# cnc_1_0_0.net
KiCad netlist of a schematic drawn in EAGLE
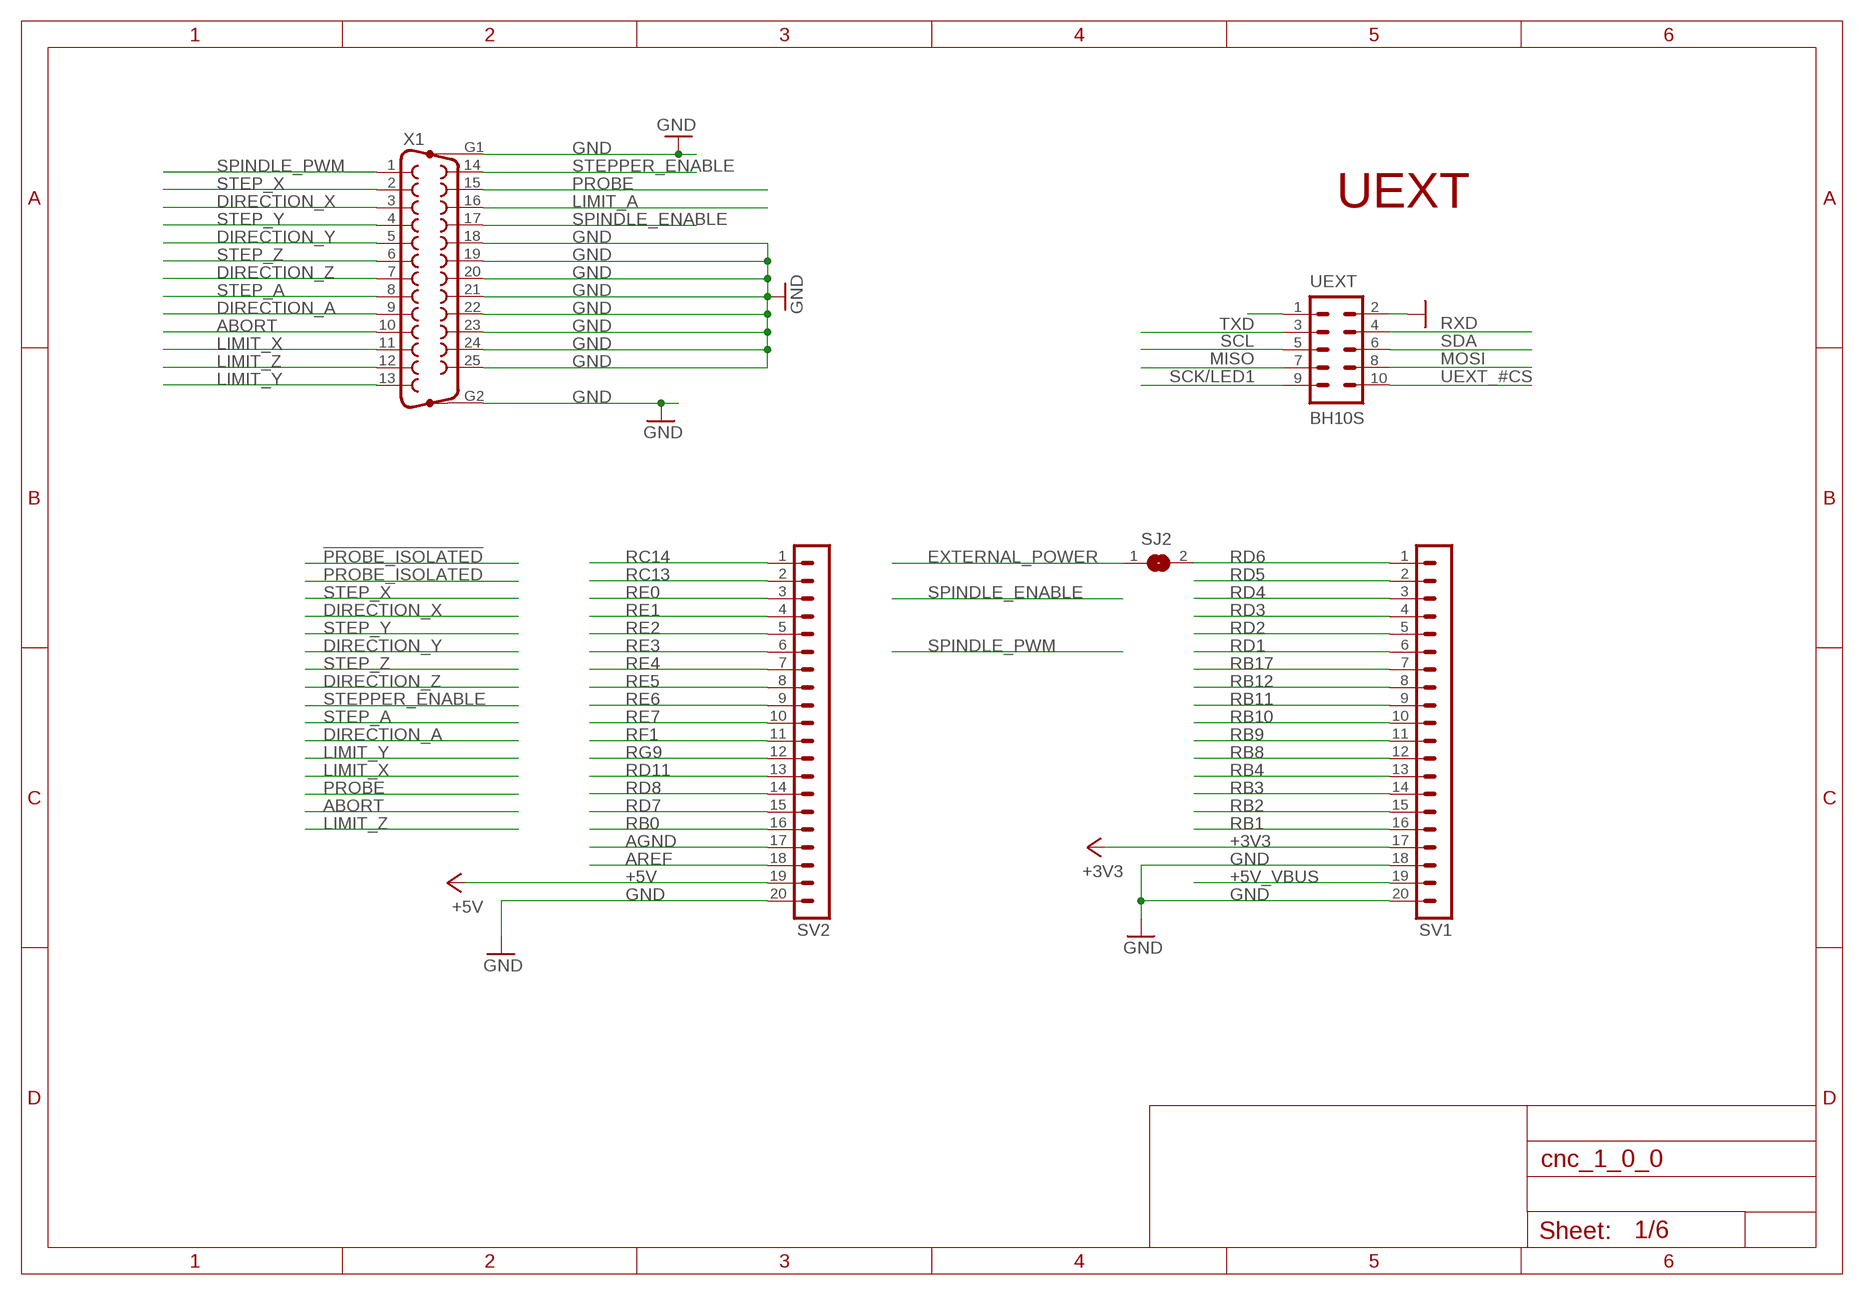
[diagram p0: schematic, sheet 1]
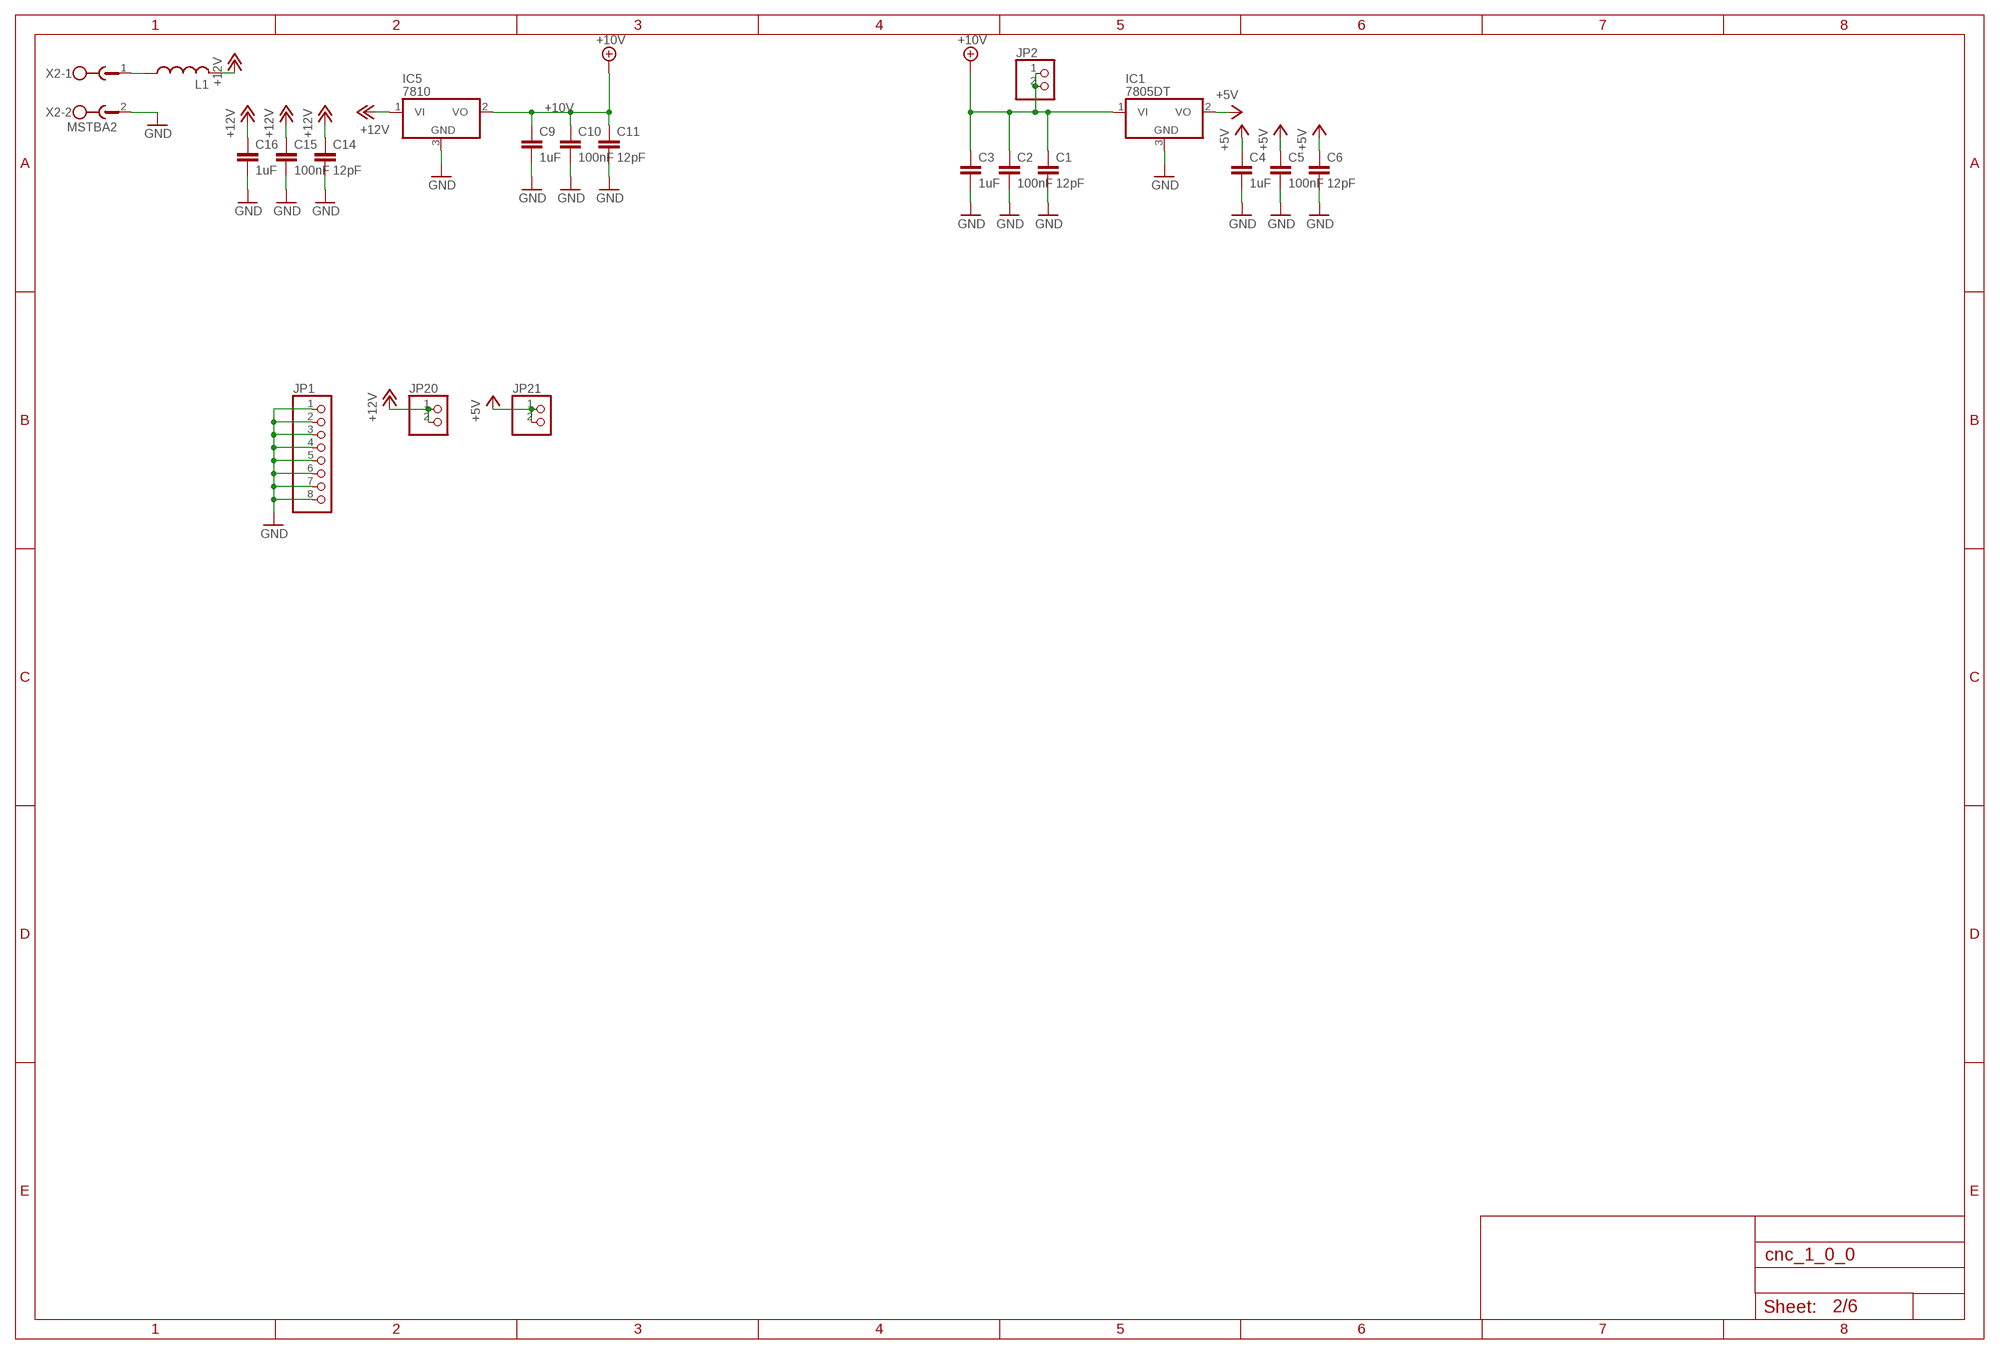
[diagram p1: schematic, sheet 2]
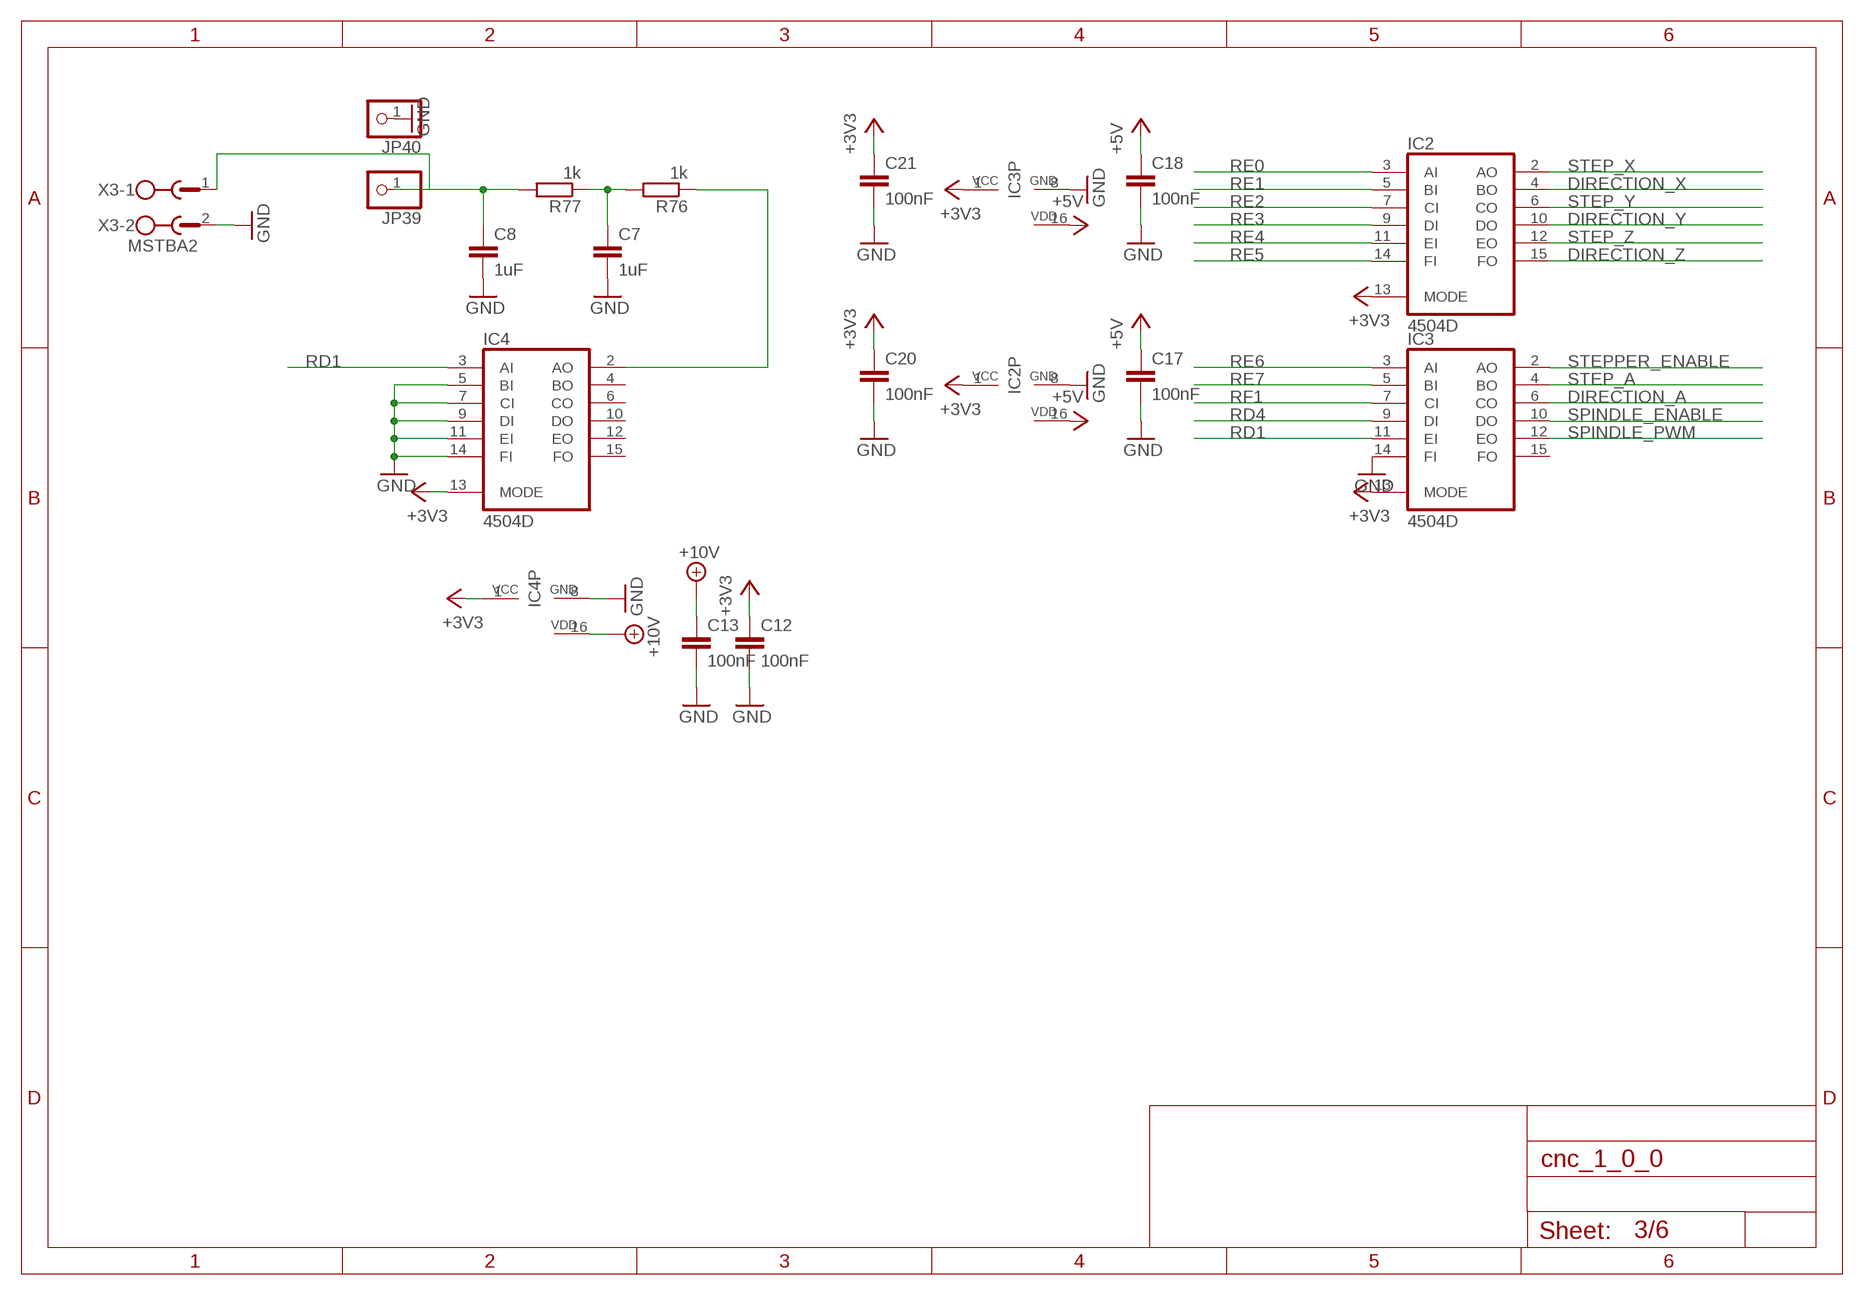
[diagram p2: schematic, sheet 3]
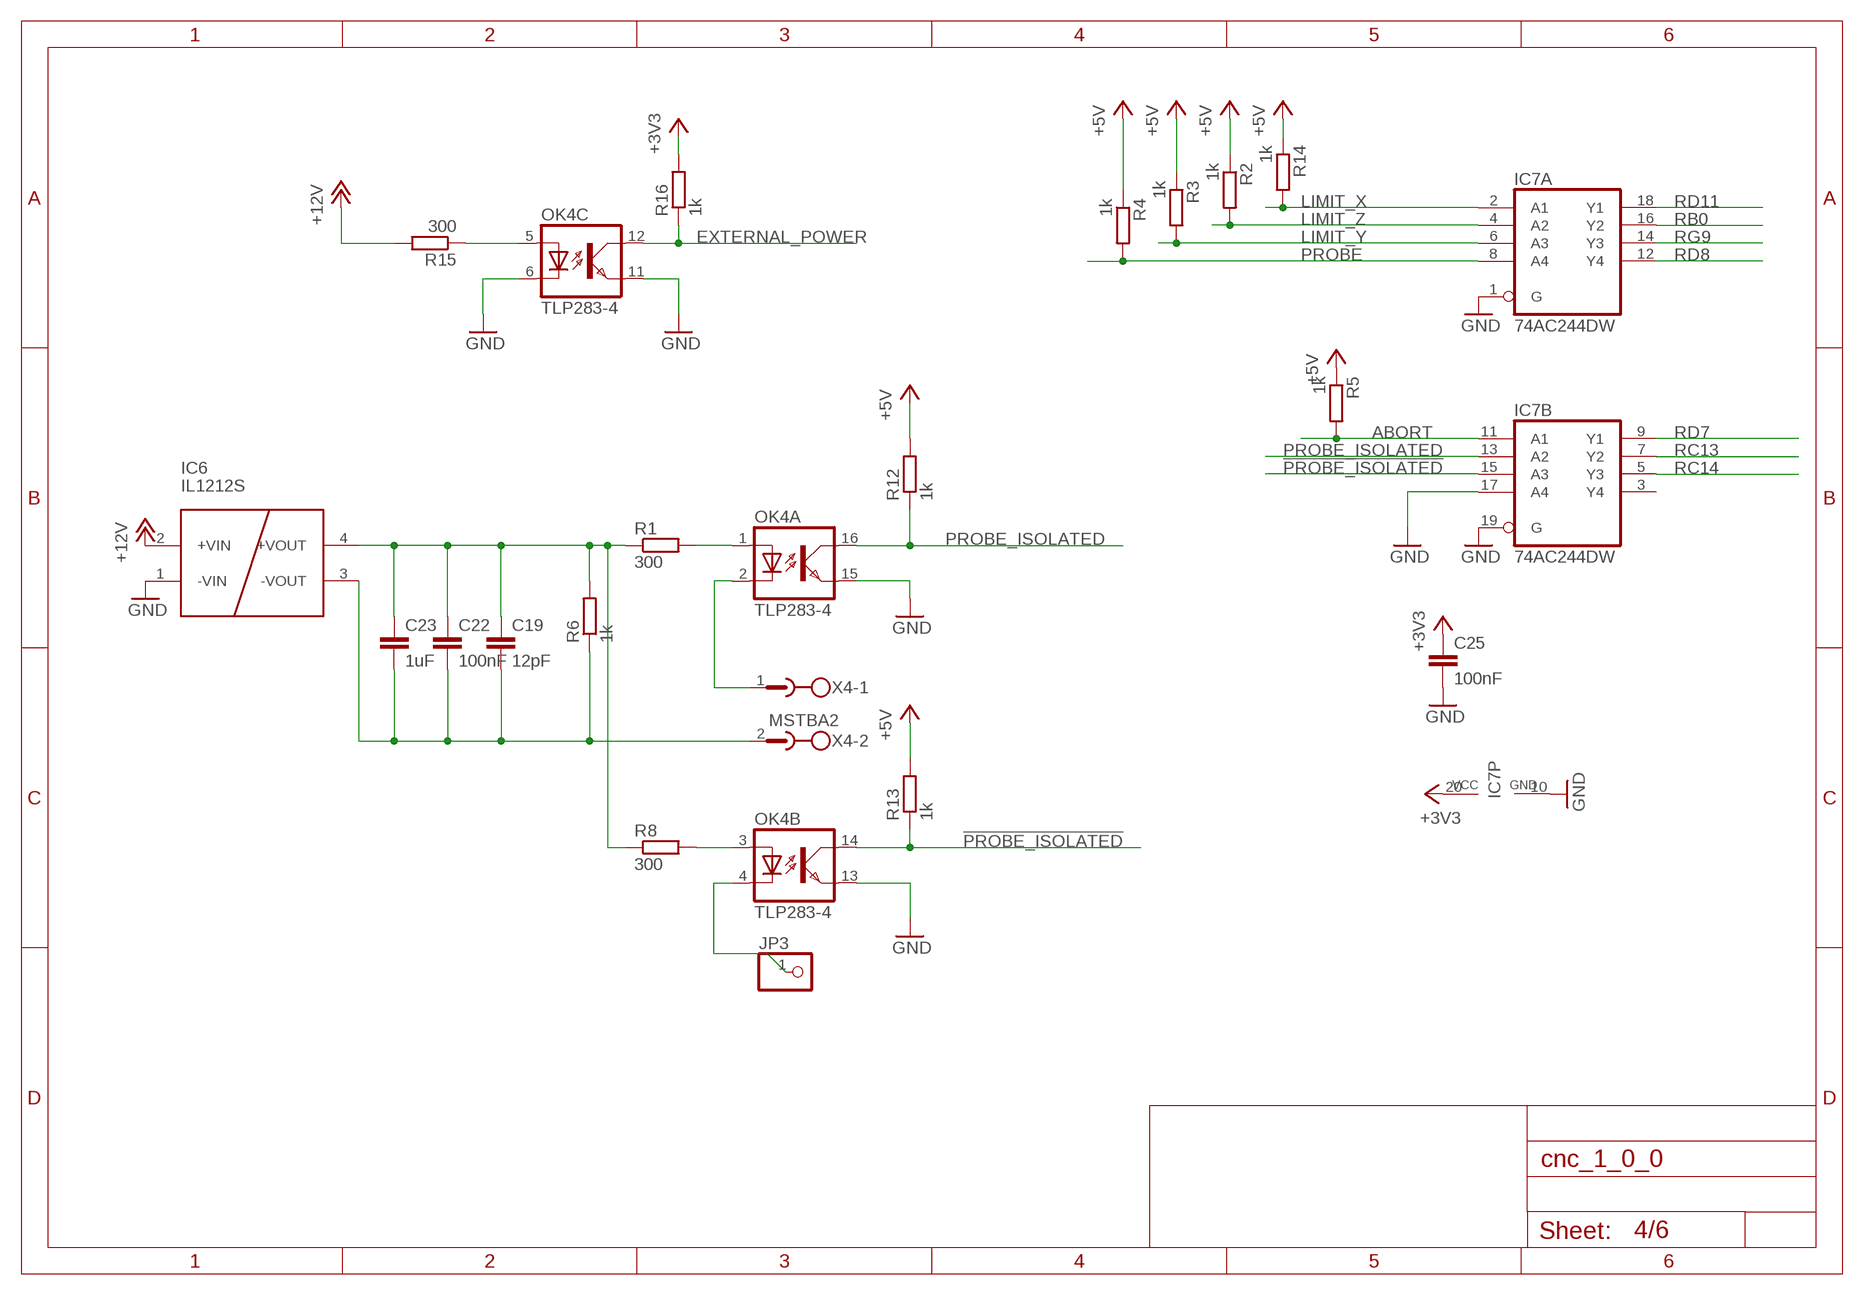
[diagram p3: schematic, sheet 4]
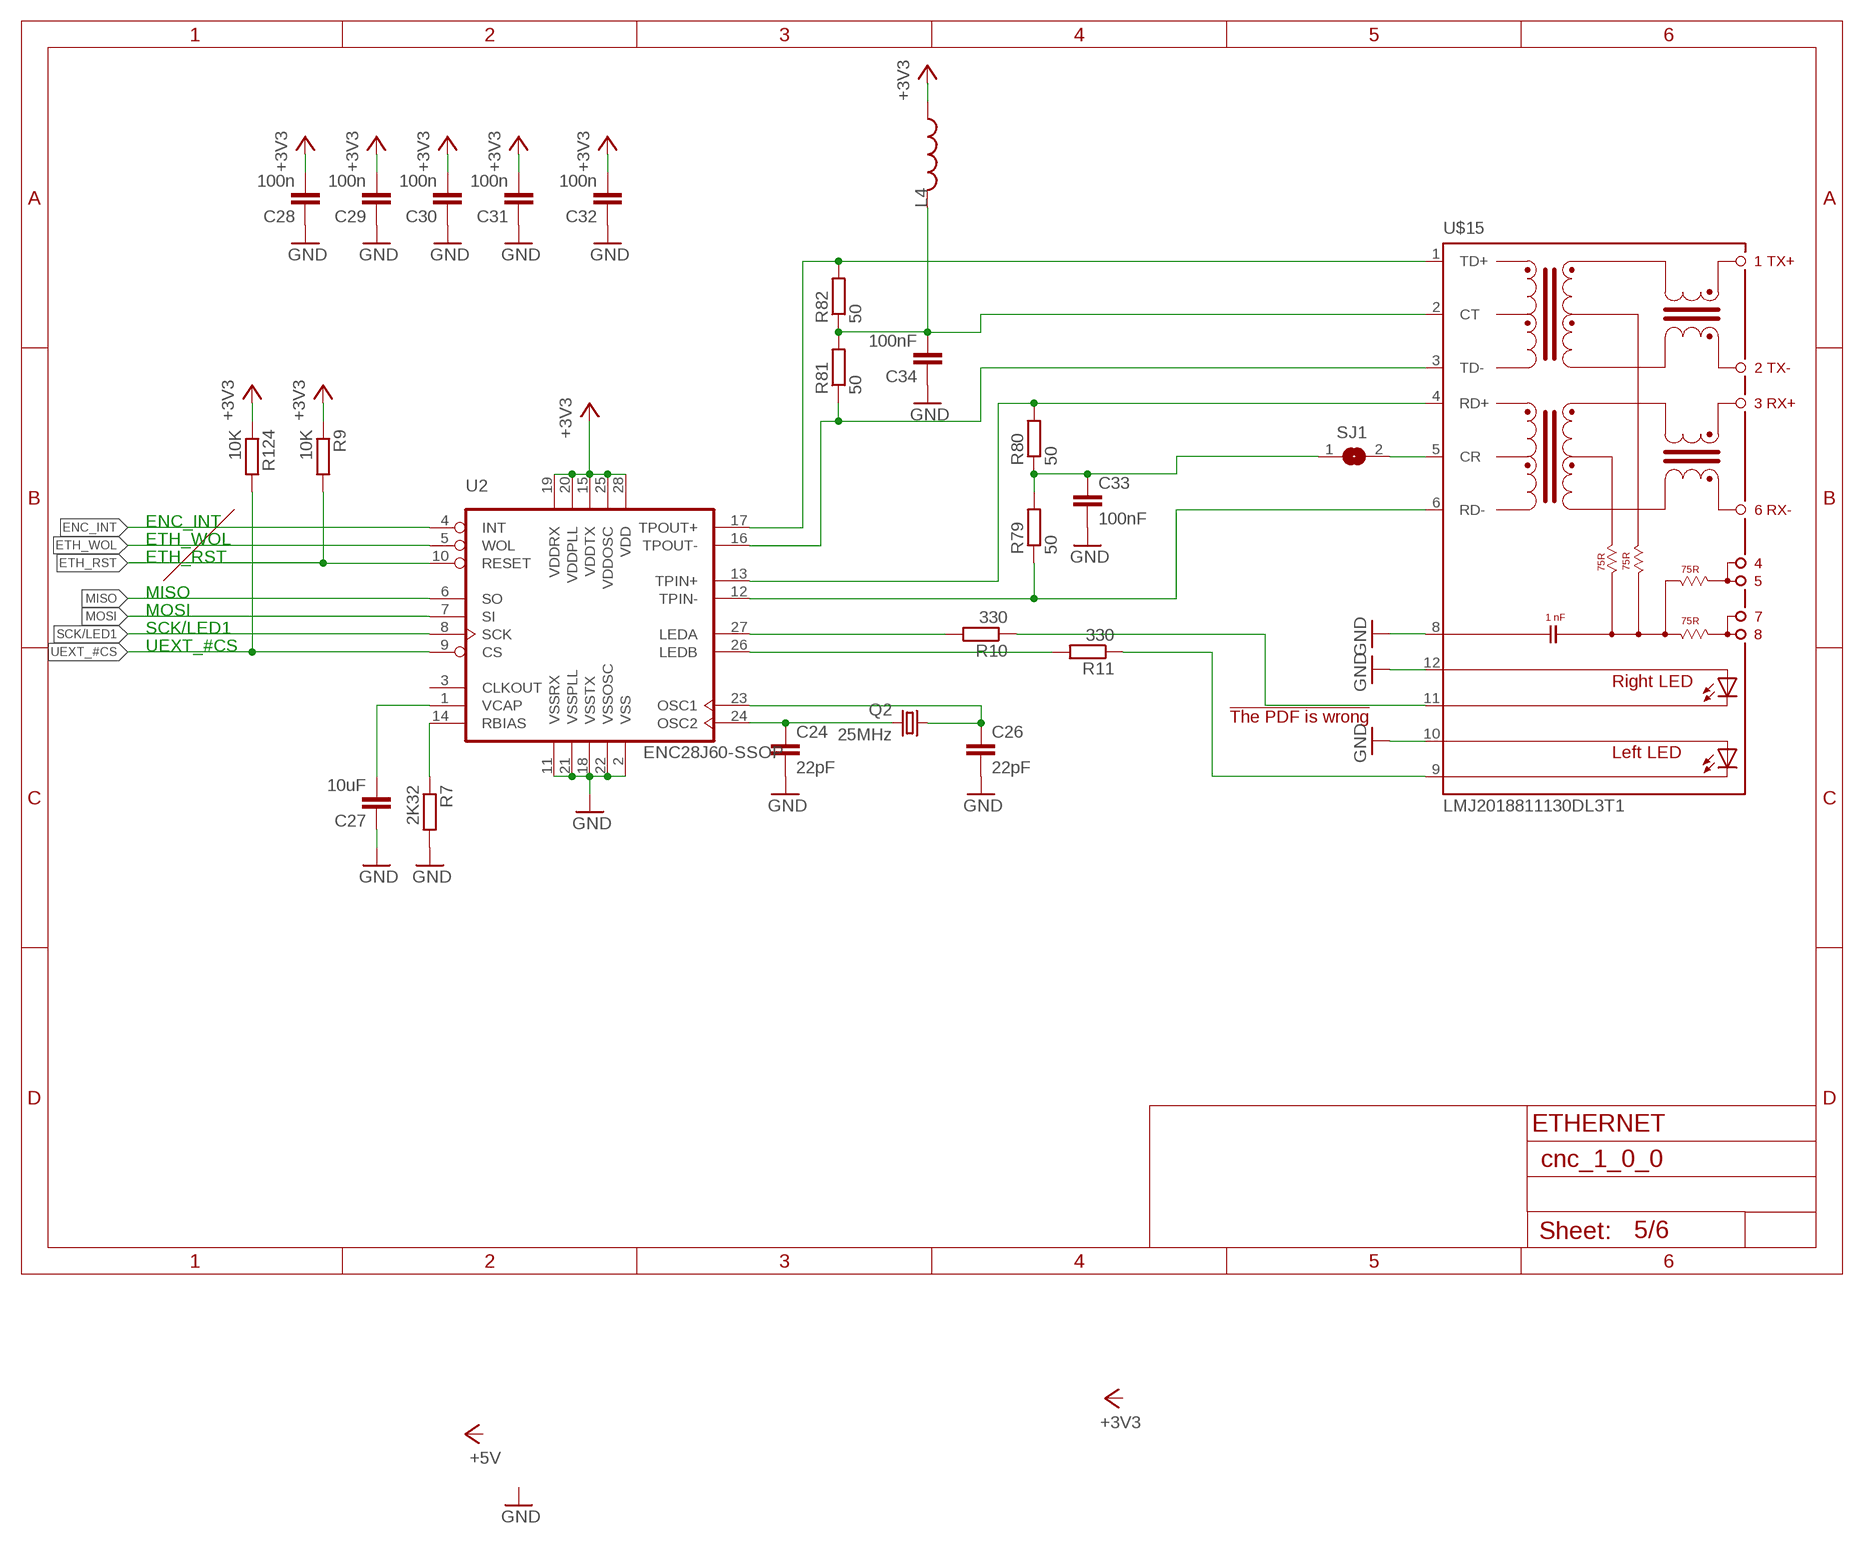
[diagram p4: schematic, sheet 5]
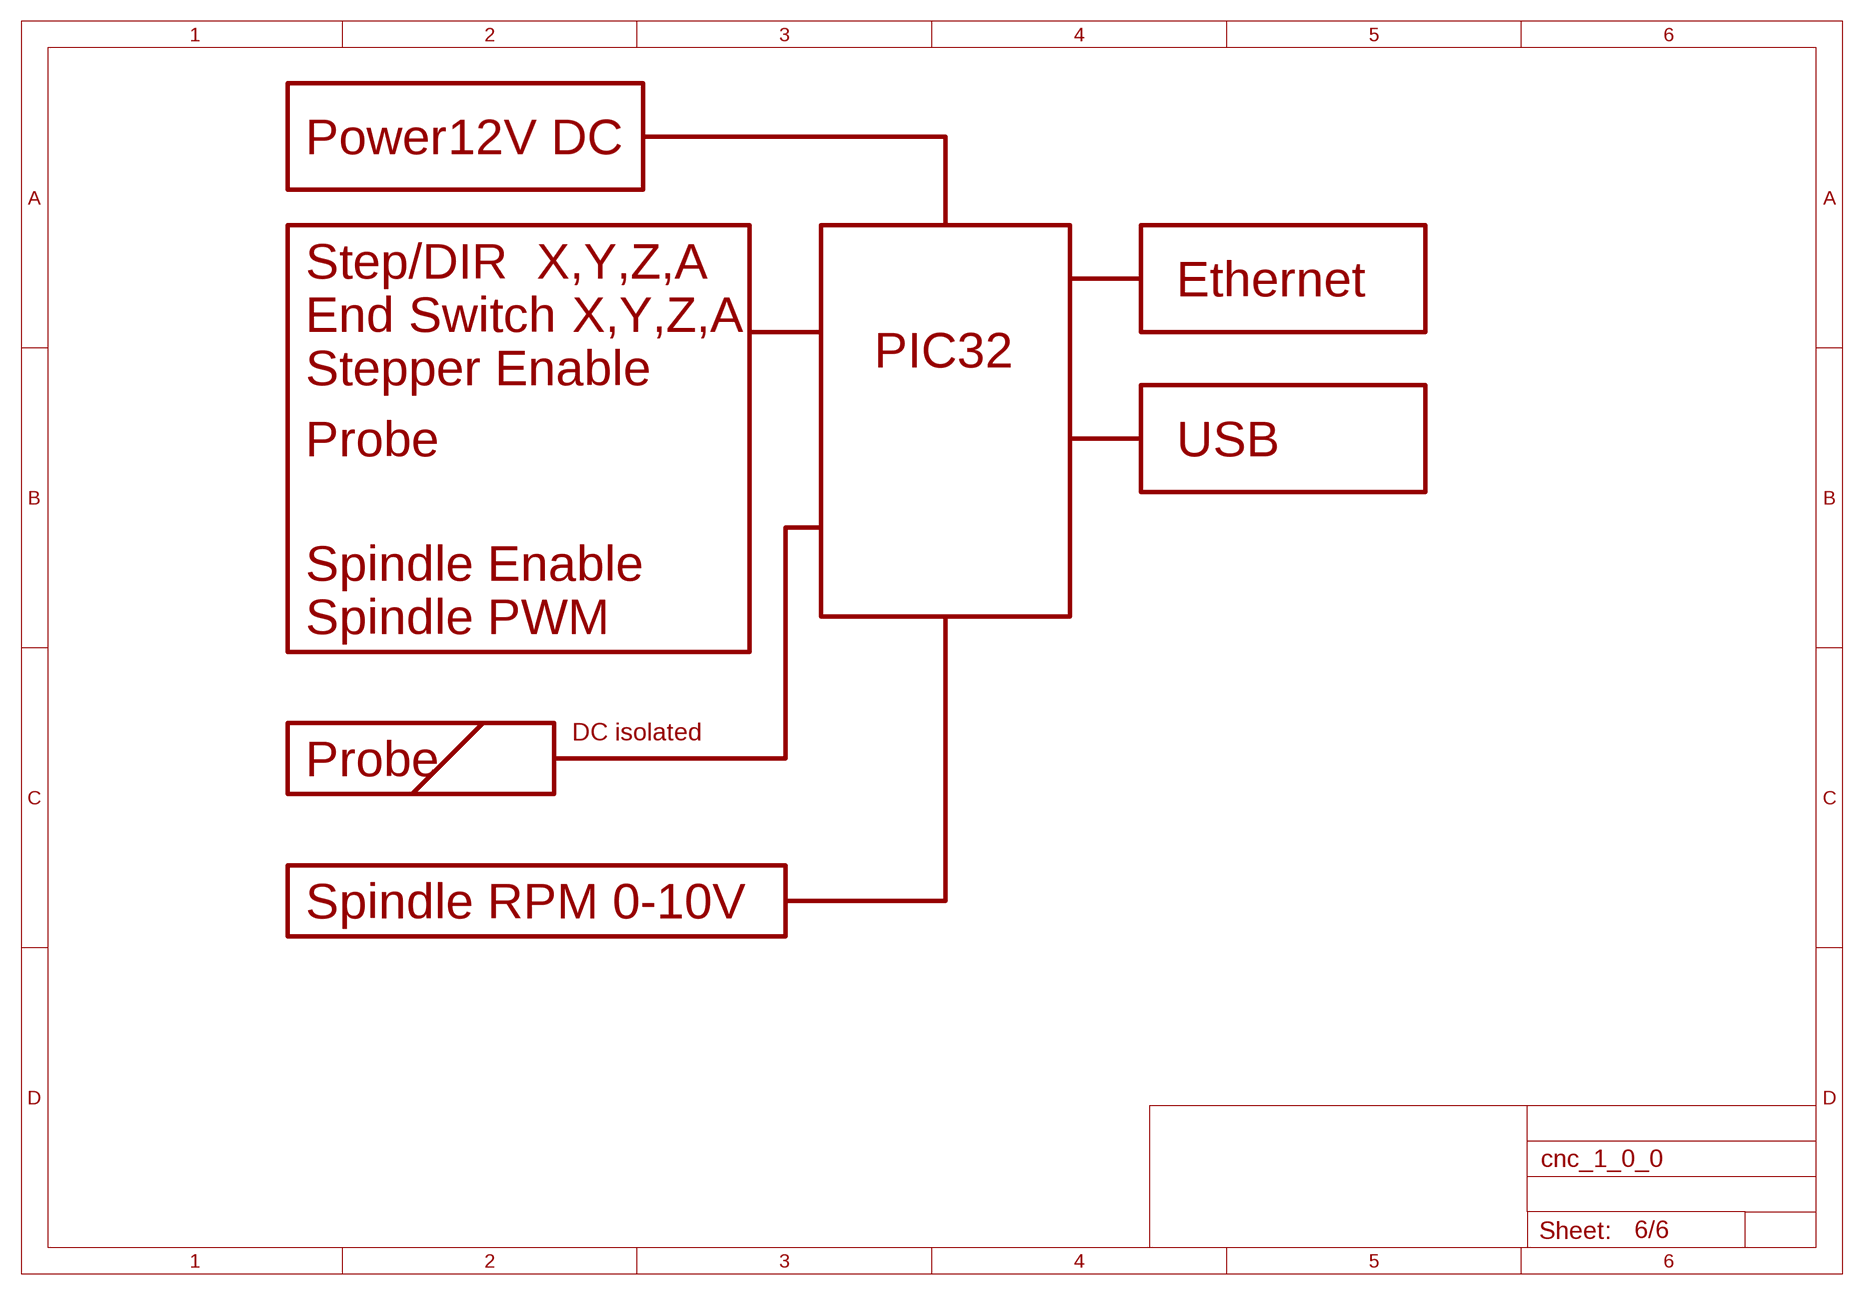
[diagram p5: schematic, sheet 6]

(export (version "E")
  (design (tool "Eeschema 10.0.6"))
  (components
    (comp (ref "C19")
      (value "12pF")
      (footprint "eagle-import:C0805K")
      (libsource (lib "eagle-import") (part "C-EUC0805K"))
    )
    (comp (ref "C22")
      (value "100nF")
      (footprint "eagle-import:C0805K")
      (libsource (lib "eagle-import") (part "C-EUC0805K"))
    )
    (comp (ref "C23")
      (value "1uF")
      (footprint "eagle-import:C0805K")
      (libsource (lib "eagle-import") (part "C-EUC0805K"))
    )
    (comp (ref "C25")
      (value "100nF")
      (footprint "eagle-import:C0805K")
      (libsource (lib "eagle-import") (part "C-EUC0805K"))
    )
    (comp (ref "IC6")
      (value "IL1212S")
      (footprint "eagle-import:SIL4")
      (libsource (lib "eagle-import") (part "IL0512S"))
    )
    (comp (ref "IC7")
      (value "74AC244DW")
      (footprint "eagle-import:SO20W")
      (libsource (lib "eagle-import") (part "74244DWAC"))
    )
    (comp (ref "JP3")
      (value "PINHD-1X1")
      (footprint "eagle-import:1X01")
      (libsource (lib "eagle-import") (part "PINHD-1X1"))
    )
    (comp (ref "OK4")
      (value "TLP283-4")
      (footprint "eagle-import:MINI-FLAT-16")
      (libsource (lib "eagle-import") (part "TLP283-4"))
    )
    (comp (ref "R1")
      (value "300")
      (footprint "eagle-import:R0805")
      (libsource (lib "eagle-import") (part "R-EU_R0805"))
    )
    (comp (ref "R2")
      (value "1k")
      (footprint "eagle-import:R0805")
      (libsource (lib "eagle-import") (part "R-EU_R0805"))
    )
    (comp (ref "R3")
      (value "1k")
      (footprint "eagle-import:R0805")
      (libsource (lib "eagle-import") (part "R-EU_R0805"))
    )
    (comp (ref "R4")
      (value "1k")
      (footprint "eagle-import:R0805")
      (libsource (lib "eagle-import") (part "R-EU_R0805"))
    )
    (comp (ref "R5")
      (value "1k")
      (footprint "eagle-import:R0805")
      (libsource (lib "eagle-import") (part "R-EU_R0805"))
    )
    (comp (ref "R6")
      (value "1k")
      (footprint "eagle-import:R0805")
      (libsource (lib "eagle-import") (part "R-EU_R0805"))
    )
    (comp (ref "R8")
      (value "300")
      (footprint "eagle-import:R0805")
      (libsource (lib "eagle-import") (part "R-EU_R0805"))
    )
    (comp (ref "R12")
      (value "1k")
      (footprint "eagle-import:R0805")
      (libsource (lib "eagle-import") (part "R-EU_R0805"))
    )
    (comp (ref "R13")
      (value "1k")
      (footprint "eagle-import:R0805")
      (libsource (lib "eagle-import") (part "R-EU_R0805"))
    )
    (comp (ref "R14")
      (value "1k")
      (footprint "eagle-import:R0805")
      (libsource (lib "eagle-import") (part "R-EU_R0805"))
    )
    (comp (ref "R15")
      (value "300")
      (footprint "eagle-import:R0805")
      (libsource (lib "eagle-import") (part "R-EU_R0805"))
    )
    (comp (ref "R16")
      (value "1k")
      (footprint "eagle-import:R0805")
      (libsource (lib "eagle-import") (part "R-EU_R0805"))
    )
    (comp (ref "X4")
      (value "MSTBA2")
      (footprint "eagle-import:MSTBA2")
      (fields
        (field (name "MF") "FARNELL")
        (field (name "MPN") "1757242")
        (field (name "MF_1") "FARNELL")
        (field (name "MPN_1") "1757242")
        (field (name "OC_FARNELL") "3705171")
        (field (name "OC_NEWARK") "71C4161")
      )
      (libsource (lib "eagle-import") (part "MSTBA2"))
    )
    (comp (ref "C1")
      (value "12pF")
      (footprint "eagle-import:C0805K")
      (libsource (lib "eagle-import") (part "C-EUC0805K"))
    )
    (comp (ref "C2")
      (value "100nF")
      (footprint "eagle-import:C0805K")
      (libsource (lib "eagle-import") (part "C-EUC0805K"))
    )
    (comp (ref "C3")
      (value "1uF")
      (footprint "eagle-import:C0805K")
      (libsource (lib "eagle-import") (part "C-EUC0805K"))
    )
    (comp (ref "C4")
      (value "1uF")
      (footprint "eagle-import:C0805K")
      (libsource (lib "eagle-import") (part "C-EUC0805K"))
    )
    (comp (ref "C5")
      (value "100nF")
      (footprint "eagle-import:C0805K")
      (libsource (lib "eagle-import") (part "C-EUC0805K"))
    )
    (comp (ref "C6")
      (value "12pF")
      (footprint "eagle-import:C0805K")
      (libsource (lib "eagle-import") (part "C-EUC0805K"))
    )
    (comp (ref "C9")
      (value "1uF")
      (footprint "eagle-import:C0805K")
      (libsource (lib "eagle-import") (part "C-EUC0805K"))
    )
    (comp (ref "C10")
      (value "100nF")
      (footprint "eagle-import:C0805K")
      (libsource (lib "eagle-import") (part "C-EUC0805K"))
    )
    (comp (ref "C11")
      (value "12pF")
      (footprint "eagle-import:C0805K")
      (libsource (lib "eagle-import") (part "C-EUC0805K"))
    )
    (comp (ref "C14")
      (value "12pF")
      (footprint "eagle-import:C0805K")
      (libsource (lib "eagle-import") (part "C-EUC0805K"))
    )
    (comp (ref "C15")
      (value "100nF")
      (footprint "eagle-import:C0805K")
      (libsource (lib "eagle-import") (part "C-EUC0805K"))
    )
    (comp (ref "C16")
      (value "1uF")
      (footprint "eagle-import:C0805K")
      (libsource (lib "eagle-import") (part "C-EUC0805K"))
    )
    (comp (ref "IC1")
      (value "7805DT")
      (footprint "eagle-import:TO252")
      (libsource (lib "eagle-import") (part "78DT05"))
    )
    (comp (ref "IC5")
      (value "7810")
      (footprint "eagle-import:TO252")
      (libsource (lib "eagle-import") (part "78DT05"))
    )
    (comp (ref "JP1")
      (value "PINHD-1X8")
      (footprint "eagle-import:1X08")
      (libsource (lib "eagle-import") (part "PINHD-1X8"))
    )
    (comp (ref "JP2")
      (value "PINHD-1X2")
      (footprint "eagle-import:1X02")
      (libsource (lib "eagle-import") (part "PINHD-1X2"))
    )
    (comp (ref "JP20")
      (value "PINHD-1X2")
      (footprint "eagle-import:1X02")
      (libsource (lib "eagle-import") (part "PINHD-1X2"))
    )
    (comp (ref "JP21")
      (value "PINHD-1X2")
      (footprint "eagle-import:1X02")
      (libsource (lib "eagle-import") (part "PINHD-1X2"))
    )
    (comp (ref "L1")
      (value "L-USL1812")
      (footprint "eagle-import:L1812")
      (libsource (lib "eagle-import") (part "L-USL1812"))
    )
    (comp (ref "X2")
      (value "MSTBA2")
      (footprint "eagle-import:MSTBA2")
      (fields (field (name "MF") "FARNELL") (field (name "MPN") "1757242"))
      (libsource (lib "eagle-import") (part "MSTBA2"))
    )
    (comp (ref "SJ2") (value "SJ") (footprint "eagle-import:SJ") (libsource (lib "eagle-import") (part "SJ")))
    (comp (ref "SV1")
      (value "MA20-1")
      (footprint "eagle-import:MA20-1")
      (libsource (lib "eagle-import") (part "MA20-1"))
    )
    (comp (ref "SV2")
      (value "MA20-1")
      (footprint "eagle-import:MA20-1")
      (libsource (lib "eagle-import") (part "MA20-1"))
    )
    (comp (ref "UEXT")
      (value "BH10S")
      (footprint "eagle-import:ML10-MALE")
      (libsource (lib "eagle-import") (part "ML10"))
    )
    (comp (ref "X1")
      (value "F25HP")
      (footprint "eagle-import:F25HP")
      (libsource (lib "eagle-import") (part "F25HP"))
    )
    (comp (ref "C7")
      (value "1uF")
      (footprint "eagle-import:C0805K")
      (libsource (lib "eagle-import") (part "C-EUC0805K"))
    )
    (comp (ref "C8")
      (value "1uF")
      (footprint "eagle-import:C0805K")
      (libsource (lib "eagle-import") (part "C-EUC0805K"))
    )
    (comp (ref "C12")
      (value "100nF")
      (footprint "eagle-import:C0805K")
      (libsource (lib "eagle-import") (part "C-EUC0805K"))
    )
    (comp (ref "C13")
      (value "100nF")
      (footprint "eagle-import:C0805K")
      (libsource (lib "eagle-import") (part "C-EUC0805K"))
    )
    (comp (ref "C17")
      (value "100nF")
      (footprint "eagle-import:C0805K")
      (libsource (lib "eagle-import") (part "C-EUC0805K"))
    )
    (comp (ref "C18")
      (value "100nF")
      (footprint "eagle-import:C0805K")
      (libsource (lib "eagle-import") (part "C-EUC0805K"))
    )
    (comp (ref "C20")
      (value "100nF")
      (footprint "eagle-import:C0805K")
      (libsource (lib "eagle-import") (part "C-EUC0805K"))
    )
    (comp (ref "C21")
      (value "100nF")
      (footprint "eagle-import:C0805K")
      (libsource (lib "eagle-import") (part "C-EUC0805K"))
    )
    (comp (ref "IC2")
      (value "4504D")
      (footprint "eagle-import:SO16")
      (libsource (lib "eagle-import") (part "4504D"))
    )
    (comp (ref "IC3")
      (value "4504D")
      (footprint "eagle-import:SO16")
      (libsource (lib "eagle-import") (part "4504D"))
    )
    (comp (ref "IC4")
      (value "4504D")
      (footprint "eagle-import:SO16")
      (libsource (lib "eagle-import") (part "4504D"))
    )
    (comp (ref "JP39")
      (value "PINHD-1X1")
      (footprint "eagle-import:1X01")
      (libsource (lib "eagle-import") (part "PINHD-1X1"))
    )
    (comp (ref "JP40")
      (value "PINHD-1X1")
      (footprint "eagle-import:1X01")
      (libsource (lib "eagle-import") (part "PINHD-1X1"))
    )
    (comp (ref "R76")
      (value "1k")
      (footprint "eagle-import:R0805")
      (libsource (lib "eagle-import") (part "R-EU_R0805"))
    )
    (comp (ref "R77")
      (value "1k")
      (footprint "eagle-import:R0805")
      (libsource (lib "eagle-import") (part "R-EU_R0805"))
    )
    (comp (ref "X3")
      (value "MSTBA2")
      (footprint "eagle-import:MSTBA2")
      (fields
        (field (name "MF") "FARNELL")
        (field (name "MPN") "1757242")
        (field (name "MF_1") "FARNELL")
        (field (name "MPN_1") "1757242")
        (field (name "OC_FARNELL") "3705171")
        (field (name "OC_NEWARK") "71C4161")
      )
      (libsource (lib "eagle-import") (part "MSTBA2"))
    )
    (comp (ref "C24")
      (value "22pF")
      (footprint "eagle-import:C0603")
      (libsource (lib "eagle-import") (part "C-EUC0603"))
    )
    (comp (ref "C26")
      (value "22pF")
      (footprint "eagle-import:C0603")
      (libsource (lib "eagle-import") (part "C-EUC0603"))
    )
    (comp (ref "C27")
      (value "10uF")
      (footprint "eagle-import:C0805K")
      (libsource (lib "eagle-import") (part "C-EUC0805K"))
    )
    (comp (ref "C28")
      (value "100n")
      (footprint "eagle-import:C0603")
      (libsource (lib "eagle-import") (part "C-EUC0603"))
    )
    (comp (ref "C29")
      (value "100n")
      (footprint "eagle-import:C0603")
      (libsource (lib "eagle-import") (part "C-EUC0603"))
    )
    (comp (ref "C30")
      (value "100n")
      (footprint "eagle-import:C0603")
      (libsource (lib "eagle-import") (part "C-EUC0603"))
    )
    (comp (ref "C31")
      (value "100n")
      (footprint "eagle-import:C0603")
      (libsource (lib "eagle-import") (part "C-EUC0603"))
    )
    (comp (ref "C32")
      (value "100n")
      (footprint "eagle-import:C0603")
      (libsource (lib "eagle-import") (part "C-EUC0603"))
    )
    (comp (ref "C33")
      (value "100nF")
      (footprint "eagle-import:C0603")
      (libsource (lib "eagle-import") (part "C-EUC0603"))
    )
    (comp (ref "C34")
      (value "100nF")
      (footprint "eagle-import:C0603")
      (libsource (lib "eagle-import") (part "C-EUC0603"))
    )
    (comp (ref "L4")
      (value "INDUCTOR0603")
      (footprint "eagle-import:0603")
      (libsource (lib "eagle-import") (part "INDUCTOR0603"))
    )
    (comp (ref "Q2")
      (value "25MHz")
      (footprint "eagle-import:CRYSTAL-SMD-5X3")
      (libsource (lib "eagle-import") (part "CRYSTAL5X3"))
    )
    (comp (ref "R7")
      (value "2K32")
      (footprint "eagle-import:R0805")
      (libsource (lib "eagle-import") (part "R-EU_R0805"))
    )
    (comp (ref "R9")
      (value "10K")
      (footprint "eagle-import:R0805")
      (libsource (lib "eagle-import") (part "R-EU_R0805"))
    )
    (comp (ref "R10")
      (value "330")
      (footprint "eagle-import:R0805")
      (libsource (lib "eagle-import") (part "R-EU_R0805"))
    )
    (comp (ref "R11")
      (value "330")
      (footprint "eagle-import:R0805")
      (libsource (lib "eagle-import") (part "R-EU_R0805"))
    )
    (comp (ref "R79")
      (value "50")
      (footprint "eagle-import:R0603")
      (libsource (lib "eagle-import") (part "R-EU_R0603"))
    )
    (comp (ref "R80")
      (value "50")
      (footprint "eagle-import:R0603")
      (libsource (lib "eagle-import") (part "R-EU_R0603"))
    )
    (comp (ref "R81")
      (value "50")
      (footprint "eagle-import:R0603")
      (libsource (lib "eagle-import") (part "R-EU_R0603"))
    )
    (comp (ref "R82")
      (value "50")
      (footprint "eagle-import:R0603")
      (libsource (lib "eagle-import") (part "R-EU_R0603"))
    )
    (comp (ref "R124")
      (value "10K")
      (footprint "eagle-import:R0805")
      (libsource (lib "eagle-import") (part "R-EU_R0805"))
    )
    (comp (ref "SJ1") (value "SJ") (footprint "eagle-import:SJ") (libsource (lib "eagle-import") (part "SJ")))
    (comp (ref "U$15")
      (value "LMJ2018811130DL3T1")
      (footprint "eagle-import:AMPHENOL-LMJ2018814100DL2T1B_RJ45")
      (libsource (lib "eagle-import") (part "AMPHENOL-LMJ2018814100DL2T1B_LMJ2018814100DL"))
    )
    (comp (ref "U2")
      (value "ENC28J60-SSOP")
      (footprint "eagle-import:SSOP28")
      (libsource (lib "eagle-import") (part "ENC28J60-SSOP"))
    )
  )
  (nets
    (net (code "1") (name "+3V3") (class "Default")
      (node (ref "C12") (pin "1") (pinfunction "1_1") (pintype "passive"))
      (node (ref "C20") (pin "1") (pinfunction "1_1") (pintype "passive"))
      (node (ref "C21") (pin "1") (pinfunction "1_1") (pintype "passive"))
      (node (ref "C25") (pin "1") (pinfunction "1_1") (pintype "passive"))
      (node (ref "C28") (pin "2") (pinfunction "2_2") (pintype "passive"))
      (node (ref "C29") (pin "2") (pinfunction "2_2") (pintype "passive"))
      (node (ref "C30") (pin "2") (pinfunction "2_2") (pintype "passive"))
      (node (ref "C31") (pin "2") (pinfunction "2_2") (pintype "passive"))
      (node (ref "C32") (pin "2") (pinfunction "2_2") (pintype "passive"))
      (node (ref "IC2") (pin "1") (pinfunction "VCC_1") (pintype "power_in"))
      (node (ref "IC2") (pin "13") (pinfunction "MODE_13") (pintype "input"))
      (node (ref "IC3") (pin "1") (pinfunction "VCC_1") (pintype "power_in"))
      (node (ref "IC3") (pin "13") (pinfunction "MODE_13") (pintype "input"))
      (node (ref "IC4") (pin "1") (pinfunction "VCC_1") (pintype "power_in"))
      (node (ref "IC4") (pin "13") (pinfunction "MODE_13") (pintype "input"))
      (node (ref "IC7") (pin "20") (pinfunction "VCC_20") (pintype "power_in"))
      (node (ref "L4") (pin "1") (pinfunction "1_1") (pintype "passive"))
      (node (ref "R124") (pin "1") (pinfunction "1_1") (pintype "passive"))
      (node (ref "R16") (pin "2") (pinfunction "2_2") (pintype "passive"))
      (node (ref "R9") (pin "1") (pinfunction "1_1") (pintype "passive"))
      (node (ref "SV1") (pin "17") (pinfunction "17_17") (pintype "passive"))
      (node (ref "U2") (pin "15") (pinfunction "VDDTX_15") (pintype "power_in"))
      (node (ref "U2") (pin "19") (pinfunction "VDDRX_19") (pintype "power_in"))
      (node (ref "U2") (pin "20") (pinfunction "VDDPLL_20") (pintype "power_in"))
      (node (ref "U2") (pin "25") (pinfunction "VDDOSC_25") (pintype "power_in"))
      (node (ref "U2") (pin "28") (pinfunction "VDD_28") (pintype "power_in"))
    )
    (net (code "2") (name "+5V") (class "Default")
      (node (ref "C17") (pin "1") (pinfunction "1_1") (pintype "passive"))
      (node (ref "C18") (pin "1") (pinfunction "1_1") (pintype "passive"))
      (node (ref "C4") (pin "1") (pinfunction "1_1") (pintype "passive"))
      (node (ref "C5") (pin "1") (pinfunction "1_1") (pintype "passive"))
      (node (ref "C6") (pin "1") (pinfunction "1_1") (pintype "passive"))
      (node (ref "IC1") (pin "2") (pinfunction "VO_2") (pintype "passive"))
      (node (ref "IC2") (pin "16") (pinfunction "VDD_16") (pintype "power_in"))
      (node (ref "IC3") (pin "16") (pinfunction "VDD_16") (pintype "power_in"))
      (node (ref "JP21") (pin "1") (pinfunction "1_1") (pintype "passive"))
      (node (ref "JP21") (pin "2") (pinfunction "2_2") (pintype "passive"))
      (node (ref "R12") (pin "2") (pinfunction "2_2") (pintype "passive"))
      (node (ref "R13") (pin "2") (pinfunction "2_2") (pintype "passive"))
      (node (ref "R14") (pin "1") (pinfunction "1_1") (pintype "passive"))
      (node (ref "R2") (pin "1") (pinfunction "1_1") (pintype "passive"))
      (node (ref "R3") (pin "1") (pinfunction "1_1") (pintype "passive"))
      (node (ref "R4") (pin "1") (pinfunction "1_1") (pintype "passive"))
      (node (ref "R5") (pin "1") (pinfunction "1_1") (pintype "passive"))
      (node (ref "SV2") (pin "19") (pinfunction "19_19") (pintype "passive"))
    )
    (net (code "3") (name "+5V_VBUS") (class "Default")
      (node (ref "SV1") (pin "19") (pinfunction "19_19") (pintype "passive"))
    )
    (net (code "4") (name "+10V") (class "Default")
      (node (ref "C1") (pin "1") (pinfunction "1_1") (pintype "passive"))
      (node (ref "C10") (pin "1") (pinfunction "1_1") (pintype "passive"))
      (node (ref "C11") (pin "1") (pinfunction "1_1") (pintype "passive"))
      (node (ref "C13") (pin "1") (pinfunction "1_1") (pintype "passive"))
      (node (ref "C2") (pin "1") (pinfunction "1_1") (pintype "passive"))
      (node (ref "C3") (pin "1") (pinfunction "1_1") (pintype "passive"))
      (node (ref "C9") (pin "1") (pinfunction "1_1") (pintype "passive"))
      (node (ref "IC1") (pin "1") (pinfunction "VI_1") (pintype "input"))
      (node (ref "IC4") (pin "16") (pinfunction "VDD_16") (pintype "power_in"))
      (node (ref "IC5") (pin "2") (pinfunction "VO_2") (pintype "passive"))
      (node (ref "JP2") (pin "1") (pinfunction "1_1") (pintype "passive"))
      (node (ref "JP2") (pin "2") (pinfunction "2_2") (pintype "passive"))
    )
    (net (code "5") (name "+12V") (class "Default")
      (node (ref "C14") (pin "1") (pinfunction "1_1") (pintype "passive"))
      (node (ref "C15") (pin "1") (pinfunction "1_1") (pintype "passive"))
      (node (ref "C16") (pin "1") (pinfunction "1_1") (pintype "passive"))
      (node (ref "IC5") (pin "1") (pinfunction "VI_1") (pintype "input"))
      (node (ref "IC6") (pin "2") (pinfunction "+VIN_2") (pintype "bidirectional"))
      (node (ref "JP20") (pin "1") (pinfunction "1_1") (pintype "passive"))
      (node (ref "JP20") (pin "2") (pinfunction "2_2") (pintype "passive"))
      (node (ref "L1") (pin "2") (pinfunction "2_2") (pintype "passive"))
      (node (ref "R15") (pin "2") (pinfunction "2_2") (pintype "passive"))
    )
    (net (code "6") (name "ABORT") (class "Default")
      (node (ref "IC7") (pin "11") (pinfunction "A1_11") (pintype "input"))
      (node (ref "R5") (pin "2") (pinfunction "2_2") (pintype "passive"))
      (node (ref "X1") (pin "10") (pinfunction "10_10") (pintype "passive"))
    )
    (net (code "7") (name "AGND") (class "Default")
      (node (ref "SV2") (pin "17") (pinfunction "17_17") (pintype "passive"))
    )
    (net (code "8") (name "AREF") (class "Default")
      (node (ref "SV2") (pin "18") (pinfunction "18_18") (pintype "passive"))
    )
    (net (code "9") (name "DIRECTION_A") (class "Default")
      (node (ref "IC3") (pin "6") (pinfunction "CO_6") (pintype "output"))
      (node (ref "X1") (pin "9") (pinfunction "9_9") (pintype "passive"))
    )
    (net (code "10") (name "DIRECTION_X") (class "Default")
      (node (ref "IC2") (pin "4") (pinfunction "BO_4") (pintype "output"))
      (node (ref "X1") (pin "3") (pinfunction "3_3") (pintype "passive"))
    )
    (net (code "11") (name "DIRECTION_Y") (class "Default")
      (node (ref "IC2") (pin "10") (pinfunction "DO_10") (pintype "output"))
      (node (ref "X1") (pin "5") (pinfunction "5_5") (pintype "passive"))
    )
    (net (code "12") (name "DIRECTION_Z") (class "Default")
      (node (ref "IC2") (pin "15") (pinfunction "FO_15") (pintype "output"))
      (node (ref "X1") (pin "7") (pinfunction "7_7") (pintype "passive"))
    )
    (net (code "13") (name "ENC_INT") (class "Default")
      (node (ref "U2") (pin "4") (pinfunction "INT_4") (pintype "output"))
    )
    (net (code "14") (name "ETH_RST") (class "Default")
      (node (ref "R9") (pin "2") (pinfunction "2_2") (pintype "passive"))
      (node (ref "U2") (pin "10") (pinfunction "RESET_10") (pintype "input"))
    )
    (net (code "15") (name "ETH_WOL") (class "Default")
      (node (ref "U2") (pin "5") (pinfunction "WOL_5") (pintype "output"))
    )
    (net (code "16") (name "EXTERNAL_POWER") (class "Default")
      (node (ref "OK4") (pin "12") (pinfunction "COL_12") (pintype "passive"))
      (node (ref "R16") (pin "1") (pinfunction "1_1") (pintype "passive"))
      (node (ref "SJ2") (pin "1") (pinfunction "1_1") (pintype "passive"))
    )
    (net (code "17") (name "GND") (class "Default")
      (node (ref "C1") (pin "2") (pinfunction "2_2") (pintype "passive"))
      (node (ref "C10") (pin "2") (pinfunction "2_2") (pintype "passive"))
      (node (ref "C11") (pin "2") (pinfunction "2_2") (pintype "passive"))
      (node (ref "C12") (pin "2") (pinfunction "2_2") (pintype "passive"))
      (node (ref "C13") (pin "2") (pinfunction "2_2") (pintype "passive"))
      (node (ref "C14") (pin "2") (pinfunction "2_2") (pintype "passive"))
      (node (ref "C15") (pin "2") (pinfunction "2_2") (pintype "passive"))
      (node (ref "C16") (pin "2") (pinfunction "2_2") (pintype "passive"))
      (node (ref "C17") (pin "2") (pinfunction "2_2") (pintype "passive"))
      (node (ref "C18") (pin "2") (pinfunction "2_2") (pintype "passive"))
      (node (ref "C2") (pin "2") (pinfunction "2_2") (pintype "passive"))
      (node (ref "C20") (pin "2") (pinfunction "2_2") (pintype "passive"))
      (node (ref "C21") (pin "2") (pinfunction "2_2") (pintype "passive"))
      (node (ref "C24") (pin "2") (pinfunction "2_2") (pintype "passive"))
      (node (ref "C25") (pin "2") (pinfunction "2_2") (pintype "passive"))
      (node (ref "C26") (pin "2") (pinfunction "2_2") (pintype "passive"))
      (node (ref "C27") (pin "1") (pinfunction "1_1") (pintype "passive"))
      (node (ref "C28") (pin "1") (pinfunction "1_1") (pintype "passive"))
      (node (ref "C29") (pin "1") (pinfunction "1_1") (pintype "passive"))
      (node (ref "C3") (pin "2") (pinfunction "2_2") (pintype "passive"))
      (node (ref "C30") (pin "1") (pinfunction "1_1") (pintype "passive"))
      (node (ref "C31") (pin "1") (pinfunction "1_1") (pintype "passive"))
      (node (ref "C32") (pin "1") (pinfunction "1_1") (pintype "passive"))
      (node (ref "C33") (pin "2") (pinfunction "2_2") (pintype "passive"))
      (node (ref "C34") (pin "1") (pinfunction "1_1") (pintype "passive"))
      (node (ref "C4") (pin "2") (pinfunction "2_2") (pintype "passive"))
      (node (ref "C5") (pin "2") (pinfunction "2_2") (pintype "passive"))
      (node (ref "C6") (pin "2") (pinfunction "2_2") (pintype "passive"))
      (node (ref "C7") (pin "2") (pinfunction "2_2") (pintype "passive"))
      (node (ref "C8") (pin "2") (pinfunction "2_2") (pintype "passive"))
      (node (ref "C9") (pin "2") (pinfunction "2_2") (pintype "passive"))
      (node (ref "IC1") (pin "3") (pinfunction "GND_3") (pintype "passive"))
      (node (ref "IC2") (pin "8") (pinfunction "GND_8") (pintype "power_in"))
      (node (ref "IC3") (pin "14") (pinfunction "FI_14") (pintype "input"))
      (node (ref "IC3") (pin "8") (pinfunction "GND_8") (pintype "power_in"))
      (node (ref "IC4") (pin "11") (pinfunction "EI_11") (pintype "input"))
      (node (ref "IC4") (pin "14") (pinfunction "FI_14") (pintype "input"))
      (node (ref "IC4") (pin "5") (pinfunction "BI_5") (pintype "input"))
      (node (ref "IC4") (pin "7") (pinfunction "CI_7") (pintype "input"))
      (node (ref "IC4") (pin "8") (pinfunction "GND_8") (pintype "power_in"))
      (node (ref "IC4") (pin "9") (pinfunction "DI_9") (pintype "input"))
      (node (ref "IC5") (pin "3") (pinfunction "GND_3") (pintype "passive"))
      (node (ref "IC6") (pin "1") (pinfunction "-VIN_1") (pintype "bidirectional"))
      (node (ref "IC7") (pin "1") (pinfunction "G_1") (pintype "input"))
      (node (ref "IC7") (pin "10") (pinfunction "GND_10") (pintype "power_in"))
      (node (ref "IC7") (pin "17") (pinfunction "A4_17") (pintype "input"))
      (node (ref "IC7") (pin "19") (pinfunction "G_19") (pintype "input"))
      (node (ref "JP1") (pin "1") (pinfunction "1_1") (pintype "passive"))
      (node (ref "JP1") (pin "2") (pinfunction "2_2") (pintype "passive"))
      (node (ref "JP1") (pin "3") (pinfunction "3_3") (pintype "passive"))
      (node (ref "JP1") (pin "4") (pinfunction "4_4") (pintype "passive"))
      (node (ref "JP1") (pin "5") (pinfunction "5_5") (pintype "passive"))
      (node (ref "JP1") (pin "6") (pinfunction "6_6") (pintype "passive"))
      (node (ref "JP1") (pin "7") (pinfunction "7_7") (pintype "passive"))
      (node (ref "JP1") (pin "8") (pinfunction "8_8") (pintype "passive"))
      (node (ref "JP40") (pin "1") (pinfunction "1_1") (pintype "passive"))
      (node (ref "OK4") (pin "11") (pinfunction "EMIT_11") (pintype "passive"))
      (node (ref "OK4") (pin "13") (pinfunction "EMIT_13") (pintype "passive"))
      (node (ref "OK4") (pin "15") (pinfunction "EMIT_15") (pintype "passive"))
      (node (ref "OK4") (pin "6") (pinfunction "C_6") (pintype "passive"))
      (node (ref "R7") (pin "2") (pinfunction "2_2") (pintype "passive"))
      (node (ref "SV1") (pin "18") (pinfunction "18_18") (pintype "passive"))
      (node (ref "SV1") (pin "20") (pinfunction "20_20") (pintype "passive"))
      (node (ref "SV2") (pin "20") (pinfunction "20_20") (pintype "passive"))
      (node (ref "U$15") (pin "10") (pinfunction "A-L_10") (pintype "passive"))
      (node (ref "U$15") (pin "12") (pinfunction "A-R_12") (pintype "passive"))
      (node (ref "U$15") (pin "8") (pinfunction "8_8") (pintype "input"))
      (node (ref "U2") (pin "11") (pinfunction "VSSRX_11") (pintype "power_in"))
      (node (ref "U2") (pin "18") (pinfunction "VSSTX_18") (pintype "power_in"))
      (node (ref "U2") (pin "2") (pinfunction "VSS_2") (pintype "power_in"))
      (node (ref "U2") (pin "21") (pinfunction "VSSPLL_21") (pintype "power_in"))
      (node (ref "U2") (pin "22") (pinfunction "VSSOSC_22") (pintype "power_in"))
      (node (ref "UEXT") (pin "2") (pinfunction "2_2") (pintype "passive"))
      (node (ref "X1") (pin "18") (pinfunction "18_18") (pintype "passive"))
      (node (ref "X1") (pin "19") (pinfunction "19_19") (pintype "passive"))
      (node (ref "X1") (pin "20") (pinfunction "20_20") (pintype "passive"))
      (node (ref "X1") (pin "21") (pinfunction "21_21") (pintype "passive"))
      (node (ref "X1") (pin "22") (pinfunction "22_22") (pintype "passive"))
      (node (ref "X1") (pin "23") (pinfunction "23_23") (pintype "passive"))
      (node (ref "X1") (pin "24") (pinfunction "24_24") (pintype "passive"))
      (node (ref "X1") (pin "25") (pinfunction "25_25") (pintype "passive"))
      (node (ref "X1") (pin "G1") (pinfunction "G1_G1") (pintype "passive"))
      (node (ref "X1") (pin "G2") (pinfunction "G2_G2") (pintype "passive"))
      (node (ref "X2") (pin "2") (pinfunction "1_2") (pintype "passive"))
      (node (ref "X3") (pin "2") (pinfunction "1_2") (pintype "passive"))
    )
    (net (code "18") (name "LIMIT_A") (class "Default")
      (node (ref "X1") (pin "16") (pinfunction "16_16") (pintype "passive"))
    )
    (net (code "19") (name "LIMIT_X") (class "Default")
      (node (ref "IC7") (pin "2") (pinfunction "A1_2") (pintype "input"))
      (node (ref "R14") (pin "2") (pinfunction "2_2") (pintype "passive"))
      (node (ref "X1") (pin "11") (pinfunction "11_11") (pintype "passive"))
    )
    (net (code "20") (name "LIMIT_Y") (class "Default")
      (node (ref "IC7") (pin "6") (pinfunction "A3_6") (pintype "input"))
      (node (ref "R3") (pin "2") (pinfunction "2_2") (pintype "passive"))
      (node (ref "X1") (pin "13") (pinfunction "13_13") (pintype "passive"))
    )
    (net (code "21") (name "LIMIT_Z") (class "Default")
      (node (ref "IC7") (pin "4") (pinfunction "A2_4") (pintype "input"))
      (node (ref "R2") (pin "2") (pinfunction "2_2") (pintype "passive"))
      (node (ref "X1") (pin "12") (pinfunction "12_12") (pintype "passive"))
    )
    (net (code "22") (name "MISO") (class "Default")
      (node (ref "U2") (pin "6") (pinfunction "SO_6") (pintype "output"))
      (node (ref "UEXT") (pin "7") (pinfunction "7_7") (pintype "passive"))
    )
    (net (code "23") (name "MOSI") (class "Default")
      (node (ref "U2") (pin "7") (pinfunction "SI_7") (pintype "input"))
      (node (ref "UEXT") (pin "8") (pinfunction "8_8") (pintype "passive"))
    )
    (net (code "24") (name "Net-(C7-Pad1)") (class "Default")
      (node (ref "C7") (pin "1") (pinfunction "1_1") (pintype "passive"))
      (node (ref "R76") (pin "2") (pinfunction "2_2") (pintype "passive"))
      (node (ref "R77") (pin "1") (pinfunction "1_1") (pintype "passive"))
    )
    (net (code "25") (name "Net-(C8-Pad1)") (class "Default")
      (node (ref "C8") (pin "1") (pinfunction "1_1") (pintype "passive"))
      (node (ref "JP39") (pin "1") (pinfunction "1_1") (pintype "passive"))
      (node (ref "R77") (pin "2") (pinfunction "2_2") (pintype "passive"))
      (node (ref "X3") (pin "1") (pinfunction "1_1") (pintype "passive"))
    )
    (net (code "26") (name "Net-(C33-Pad1)") (class "Default")
      (node (ref "C33") (pin "1") (pinfunction "1_1") (pintype "passive"))
      (node (ref "R79") (pin "2") (pinfunction "2_2") (pintype "passive"))
      (node (ref "R80") (pin "1") (pinfunction "1_1") (pintype "passive"))
      (node (ref "SJ1") (pin "1") (pinfunction "1_1") (pintype "passive"))
    )
    (net (code "27") (name "Net-(IC4A-AO)") (class "Default")
      (node (ref "IC4") (pin "2") (pinfunction "AO_2") (pintype "output"))
      (node (ref "R76") (pin "1") (pinfunction "1_1") (pintype "passive"))
    )
    (net (code "28") (name "Net-(IC6-+VOUT)") (class "Default")
      (node (ref "C19") (pin "1") (pinfunction "1_1") (pintype "passive"))
      (node (ref "C22") (pin "1") (pinfunction "1_1") (pintype "passive"))
      (node (ref "C23") (pin "1") (pinfunction "1_1") (pintype "passive"))
      (node (ref "IC6") (pin "4") (pinfunction "+VOUT_4") (pintype "bidirectional"))
      (node (ref "R1") (pin "1") (pinfunction "1_1") (pintype "passive"))
      (node (ref "R6") (pin "2") (pinfunction "2_2") (pintype "passive"))
      (node (ref "R8") (pin "1") (pinfunction "1_1") (pintype "passive"))
    )
    (net (code "29") (name "Net-(IC6--VOUT)") (class "Default")
      (node (ref "C19") (pin "2") (pinfunction "2_2") (pintype "passive"))
      (node (ref "C22") (pin "2") (pinfunction "2_2") (pintype "passive"))
      (node (ref "C23") (pin "2") (pinfunction "2_2") (pintype "passive"))
      (node (ref "IC6") (pin "3") (pinfunction "-VOUT_3") (pintype "bidirectional"))
      (node (ref "R6") (pin "1") (pinfunction "1_1") (pintype "passive"))
      (node (ref "X4") (pin "2") (pinfunction "1_2") (pintype "passive"))
    )
    (net (code "30") (name "Net-(L1-Pad1)") (class "Default")
      (node (ref "L1") (pin "1") (pinfunction "1_1") (pintype "passive"))
      (node (ref "X2") (pin "1") (pinfunction "1_1") (pintype "passive"))
    )
    (net (code "31") (name "Net-(OK4A-A)") (class "Default")
      (node (ref "OK4") (pin "1") (pinfunction "A_1") (pintype "passive"))
      (node (ref "R1") (pin "2") (pinfunction "2_2") (pintype "passive"))
    )
    (net (code "32") (name "Net-(OK4A-C)") (class "Default")
      (node (ref "OK4") (pin "2") (pinfunction "C_2") (pintype "passive"))
      (node (ref "X4") (pin "1") (pinfunction "1_1") (pintype "passive"))
    )
    (net (code "33") (name "Net-(OK4B-A)") (class "Default")
      (node (ref "OK4") (pin "3") (pinfunction "A_3") (pintype "passive"))
      (node (ref "R8") (pin "2") (pinfunction "2_2") (pintype "passive"))
    )
    (net (code "34") (name "Net-(OK4B-C)") (class "Default")
      (node (ref "JP3") (pin "1") (pinfunction "1_1") (pintype "passive"))
      (node (ref "OK4") (pin "4") (pinfunction "C_4") (pintype "passive"))
    )
    (net (code "35") (name "Net-(OK4C-A)") (class "Default")
      (node (ref "OK4") (pin "5") (pinfunction "A_5") (pintype "passive"))
      (node (ref "R15") (pin "1") (pinfunction "1_1") (pintype "passive"))
    )
    (net (code "36") (name "Net-(Q2-2)") (class "Default")
      (node (ref "C24") (pin "1") (pinfunction "1_1") (pintype "passive"))
      (node (ref "Q2") (pin "3") (pinfunction "2_3") (pintype "passive"))
      (node (ref "U2") (pin "24") (pinfunction "OSC2_24") (pintype "output"))
    )
    (net (code "37") (name "Net-(U$15-C-L)") (class "Default")
      (node (ref "R11") (pin "1") (pinfunction "1_1") (pintype "passive"))
      (node (ref "U$15") (pin "9") (pinfunction "C-L_9") (pintype "passive"))
    )
    (net (code "38") (name "Net-(U$15-C-R)") (class "Default")
      (node (ref "R10") (pin "1") (pinfunction "1_1") (pintype "passive"))
      (node (ref "U$15") (pin "11") (pinfunction "C-R_11") (pintype "passive"))
    )
    (net (code "39") (name "Net-(U$15-CR)") (class "Default")
      (node (ref "SJ1") (pin "2") (pinfunction "2_2") (pintype "passive"))
      (node (ref "U$15") (pin "5") (pinfunction "CR_5") (pintype "input"))
    )
    (net (code "40") (name "Net-(U$15-CT)") (class "Default")
      (node (ref "C34") (pin "2") (pinfunction "2_2") (pintype "passive"))
      (node (ref "L4") (pin "2") (pinfunction "2_2") (pintype "passive"))
      (node (ref "R81") (pin "2") (pinfunction "2_2") (pintype "passive"))
      (node (ref "R82") (pin "1") (pinfunction "1_1") (pintype "passive"))
      (node (ref "U$15") (pin "2") (pinfunction "CT_2") (pintype "input"))
    )
    (net (code "41") (name "Net-(U$15-RD+)") (class "Default")
      (node (ref "R80") (pin "2") (pinfunction "2_2") (pintype "passive"))
      (node (ref "U$15") (pin "4") (pinfunction "RD+_4") (pintype "input"))
      (node (ref "U2") (pin "13") (pinfunction "TPIN+_13") (pintype "input"))
    )
    (net (code "42") (name "Net-(U$15-RD-)") (class "Default")
      (node (ref "R79") (pin "1") (pinfunction "1_1") (pintype "passive"))
      (node (ref "U$15") (pin "6") (pinfunction "RD-_6") (pintype "input"))
      (node (ref "U2") (pin "12") (pinfunction "TPIN-_12") (pintype "input"))
    )
    (net (code "43") (name "Net-(U$15-TD+)") (class "Default")
      (node (ref "R82") (pin "2") (pinfunction "2_2") (pintype "passive"))
      (node (ref "U$15") (pin "1") (pinfunction "TD+_1") (pintype "input"))
      (node (ref "U2") (pin "17") (pinfunction "TPOUT+_17") (pintype "output"))
    )
    (net (code "44") (name "Net-(U$15-TD-)") (class "Default")
      (node (ref "R81") (pin "1") (pinfunction "1_1") (pintype "passive"))
      (node (ref "U$15") (pin "3") (pinfunction "TD-_3") (pintype "input"))
      (node (ref "U2") (pin "16") (pinfunction "TPOUT-_16") (pintype "output"))
    )
    (net (code "45") (name "Net-(U2-LEDA)") (class "Default")
      (node (ref "R10") (pin "2") (pinfunction "2_2") (pintype "passive"))
      (node (ref "U2") (pin "27") (pinfunction "LEDA_27") (pintype "output"))
    )
    (net (code "46") (name "Net-(U2-LEDB)") (class "Default")
      (node (ref "R11") (pin "2") (pinfunction "2_2") (pintype "passive"))
      (node (ref "U2") (pin "26") (pinfunction "LEDB_26") (pintype "output"))
    )
    (net (code "47") (name "Net-(U2-OSC1)") (class "Default")
      (node (ref "C26") (pin "1") (pinfunction "1_1") (pintype "passive"))
      (node (ref "Q2") (pin "1") (pinfunction "1_1") (pintype "passive"))
      (node (ref "U2") (pin "23") (pinfunction "OSC1_23") (pintype "input"))
    )
    (net (code "48") (name "Net-(U2-RBIAS)") (class "Default")
      (node (ref "R7") (pin "1") (pinfunction "1_1") (pintype "passive"))
      (node (ref "U2") (pin "14") (pinfunction "RBIAS_14") (pintype "passive"))
    )
    (net (code "49") (name "Net-(U2-VCAP)") (class "Default")
      (node (ref "C27") (pin "2") (pinfunction "2_2") (pintype "passive"))
      (node (ref "U2") (pin "1") (pinfunction "VCAP_1") (pintype "power_in"))
    )
    (net (code "50") (name "PROBE") (class "Default")
      (node (ref "IC7") (pin "8") (pinfunction "A4_8") (pintype "input"))
      (node (ref "R4") (pin "2") (pinfunction "2_2") (pintype "passive"))
      (node (ref "X1") (pin "15") (pinfunction "15_15") (pintype "passive"))
    )
    (net (code "51") (name "PROBE_ISOLATED") (class "Default")
      (node (ref "IC7") (pin "13") (pinfunction "A2_13") (pintype "input"))
      (node (ref "OK4") (pin "16") (pinfunction "COL_16") (pintype "passive"))
      (node (ref "R12") (pin "1") (pinfunction "1_1") (pintype "passive"))
    )
    (net (code "52") (name "RB0") (class "Default")
      (node (ref "IC7") (pin "16") (pinfunction "Y2_16") (pintype "tri_state"))
      (node (ref "SV2") (pin "16") (pinfunction "16_16") (pintype "passive"))
    )
    (net (code "53") (name "RB1") (class "Default")
      (node (ref "SV1") (pin "16") (pinfunction "16_16") (pintype "passive"))
    )
    (net (code "54") (name "RB2") (class "Default")
      (node (ref "SV1") (pin "15") (pinfunction "15_15") (pintype "passive"))
    )
    (net (code "55") (name "RB3") (class "Default")
      (node (ref "SV1") (pin "14") (pinfunction "14_14") (pintype "passive"))
    )
    (net (code "56") (name "RB4") (class "Default")
      (node (ref "SV1") (pin "13") (pinfunction "13_13") (pintype "passive"))
    )
    (net (code "57") (name "RB8") (class "Default")
      (node (ref "SV1") (pin "12") (pinfunction "12_12") (pintype "passive"))
    )
    (net (code "58") (name "RB9") (class "Default")
      (node (ref "SV1") (pin "11") (pinfunction "11_11") (pintype "passive"))
    )
    (net (code "59") (name "RB10") (class "Default")
      (node (ref "SV1") (pin "10") (pinfunction "10_10") (pintype "passive"))
    )
    (net (code "60") (name "RB11") (class "Default")
      (node (ref "SV1") (pin "9") (pinfunction "9_9") (pintype "passive"))
    )
    (net (code "61") (name "RB12") (class "Default")
      (node (ref "SV1") (pin "8") (pinfunction "8_8") (pintype "passive"))
    )
    (net (code "62") (name "RB17") (class "Default")
      (node (ref "SV1") (pin "7") (pinfunction "7_7") (pintype "passive"))
    )
    (net (code "63") (name "RC13") (class "Default")
      (node (ref "IC7") (pin "7") (pinfunction "Y2_7") (pintype "tri_state"))
      (node (ref "SV2") (pin "2") (pinfunction "2_2") (pintype "passive"))
    )
    (net (code "64") (name "RC14") (class "Default")
      (node (ref "IC7") (pin "5") (pinfunction "Y3_5") (pintype "tri_state"))
      (node (ref "SV2") (pin "1") (pinfunction "1_1") (pintype "passive"))
    )
    (net (code "65") (name "RD1") (class "Default")
      (node (ref "IC3") (pin "11") (pinfunction "EI_11") (pintype "input"))
      (node (ref "IC4") (pin "3") (pinfunction "AI_3") (pintype "input"))
      (node (ref "SV1") (pin "6") (pinfunction "6_6") (pintype "passive"))
    )
    (net (code "66") (name "RD2") (class "Default")
      (node (ref "SV1") (pin "5") (pinfunction "5_5") (pintype "passive"))
    )
    (net (code "67") (name "RD3") (class "Default")
      (node (ref "SV1") (pin "4") (pinfunction "4_4") (pintype "passive"))
    )
    (net (code "68") (name "RD4") (class "Default")
      (node (ref "IC3") (pin "9") (pinfunction "DI_9") (pintype "input"))
      (node (ref "SV1") (pin "3") (pinfunction "3_3") (pintype "passive"))
    )
    (net (code "69") (name "RD5") (class "Default")
      (node (ref "SV1") (pin "2") (pinfunction "2_2") (pintype "passive"))
    )
    (net (code "70") (name "RD6") (class "Default")
      (node (ref "SJ2") (pin "2") (pinfunction "2_2") (pintype "passive"))
      (node (ref "SV1") (pin "1") (pinfunction "1_1") (pintype "passive"))
    )
    (net (code "71") (name "RD7") (class "Default")
      (node (ref "IC7") (pin "9") (pinfunction "Y1_9") (pintype "tri_state"))
      (node (ref "SV2") (pin "15") (pinfunction "15_15") (pintype "passive"))
    )
    (net (code "72") (name "RD8") (class "Default")
      (node (ref "IC7") (pin "12") (pinfunction "Y4_12") (pintype "tri_state"))
      (node (ref "SV2") (pin "14") (pinfunction "14_14") (pintype "passive"))
    )
    (net (code "73") (name "RD11") (class "Default")
      (node (ref "IC7") (pin "18") (pinfunction "Y1_18") (pintype "tri_state"))
      (node (ref "SV2") (pin "13") (pinfunction "13_13") (pintype "passive"))
    )
    (net (code "74") (name "RE0") (class "Default")
      (node (ref "IC2") (pin "3") (pinfunction "AI_3") (pintype "input"))
      (node (ref "SV2") (pin "3") (pinfunction "3_3") (pintype "passive"))
    )
    (net (code "75") (name "RE1") (class "Default")
      (node (ref "IC2") (pin "5") (pinfunction "BI_5") (pintype "input"))
      (node (ref "SV2") (pin "4") (pinfunction "4_4") (pintype "passive"))
    )
    (net (code "76") (name "RE2") (class "Default")
      (node (ref "IC2") (pin "7") (pinfunction "CI_7") (pintype "input"))
      (node (ref "SV2") (pin "5") (pinfunction "5_5") (pintype "passive"))
    )
    (net (code "77") (name "RE3") (class "Default")
      (node (ref "IC2") (pin "9") (pinfunction "DI_9") (pintype "input"))
      (node (ref "SV2") (pin "6") (pinfunction "6_6") (pintype "passive"))
    )
    (net (code "78") (name "RE4") (class "Default")
      (node (ref "IC2") (pin "11") (pinfunction "EI_11") (pintype "input"))
      (node (ref "SV2") (pin "7") (pinfunction "7_7") (pintype "passive"))
    )
    (net (code "79") (name "RE5") (class "Default")
      (node (ref "IC2") (pin "14") (pinfunction "FI_14") (pintype "input"))
      (node (ref "SV2") (pin "8") (pinfunction "8_8") (pintype "passive"))
    )
    (net (code "80") (name "RE6") (class "Default")
      (node (ref "IC3") (pin "3") (pinfunction "AI_3") (pintype "input"))
      (node (ref "SV2") (pin "9") (pinfunction "9_9") (pintype "passive"))
    )
    (net (code "81") (name "RE7") (class "Default")
      (node (ref "IC3") (pin "5") (pinfunction "BI_5") (pintype "input"))
      (node (ref "SV2") (pin "10") (pinfunction "10_10") (pintype "passive"))
    )
    (net (code "82") (name "RF1") (class "Default")
      (node (ref "IC3") (pin "7") (pinfunction "CI_7") (pintype "input"))
      (node (ref "SV2") (pin "11") (pinfunction "11_11") (pintype "passive"))
    )
    (net (code "83") (name "RG9") (class "Default")
      (node (ref "IC7") (pin "14") (pinfunction "Y3_14") (pintype "tri_state"))
      (node (ref "SV2") (pin "12") (pinfunction "12_12") (pintype "passive"))
    )
    (net (code "84") (name "RXD") (class "Default")
      (node (ref "UEXT") (pin "4") (pinfunction "4_4") (pintype "passive"))
    )
    (net (code "85") (name "SCK{slash}LED1") (class "Default")
      (node (ref "U2") (pin "8") (pinfunction "SCK_8") (pintype "input"))
      (node (ref "UEXT") (pin "9") (pinfunction "9_9") (pintype "passive"))
    )
    (net (code "86") (name "SCL") (class "Default")
      (node (ref "UEXT") (pin "5") (pinfunction "5_5") (pintype "passive"))
    )
    (net (code "87") (name "SDA") (class "Default")
      (node (ref "UEXT") (pin "6") (pinfunction "6_6") (pintype "passive"))
    )
    (net (code "88") (name "SPINDLE_ENABLE") (class "Default")
      (node (ref "IC3") (pin "10") (pinfunction "DO_10") (pintype "output"))
      (node (ref "X1") (pin "17") (pinfunction "17_17") (pintype "passive"))
    )
    (net (code "89") (name "SPINDLE_PWM") (class "Default")
      (node (ref "IC3") (pin "12") (pinfunction "EO_12") (pintype "output"))
      (node (ref "X1") (pin "1") (pinfunction "1_1") (pintype "passive"))
    )
    (net (code "90") (name "STEPPER_ENABLE") (class "Default")
      (node (ref "IC3") (pin "2") (pinfunction "AO_2") (pintype "output"))
      (node (ref "X1") (pin "14") (pinfunction "14_14") (pintype "passive"))
    )
    (net (code "91") (name "STEP_A") (class "Default")
      (node (ref "IC3") (pin "4") (pinfunction "BO_4") (pintype "output"))
      (node (ref "X1") (pin "8") (pinfunction "8_8") (pintype "passive"))
    )
    (net (code "92") (name "STEP_X") (class "Default")
      (node (ref "IC2") (pin "2") (pinfunction "AO_2") (pintype "output"))
      (node (ref "X1") (pin "2") (pinfunction "2_2") (pintype "passive"))
    )
    (net (code "93") (name "STEP_Y") (class "Default")
      (node (ref "IC2") (pin "6") (pinfunction "CO_6") (pintype "output"))
      (node (ref "X1") (pin "4") (pinfunction "4_4") (pintype "passive"))
    )
    (net (code "94") (name "STEP_Z") (class "Default")
      (node (ref "IC2") (pin "12") (pinfunction "EO_12") (pintype "output"))
      (node (ref "X1") (pin "6") (pinfunction "6_6") (pintype "passive"))
    )
    (net (code "95") (name "TXD") (class "Default")
      (node (ref "UEXT") (pin "3") (pinfunction "3_3") (pintype "passive"))
    )
    (net (code "96") (name "UEXT_#CS") (class "Default")
      (node (ref "R124") (pin "2") (pinfunction "2_2") (pintype "passive"))
      (node (ref "U2") (pin "9") (pinfunction "CS_9") (pintype "input"))
      (node (ref "UEXT") (pin "10") (pinfunction "10_10") (pintype "passive"))
    )
    (net (code "97") (name "unconnected-(IC3A-FO-Pad15)") (class "Default")
      (node (ref "IC3") (pin "15") (pinfunction "FO_15") (pintype "output"))
    )
    (net (code "98") (name "unconnected-(IC4A-BO-Pad4)") (class "Default")
      (node (ref "IC4") (pin "4") (pinfunction "BO_4") (pintype "output"))
    )
    (net (code "99") (name "unconnected-(IC4A-CO-Pad6)") (class "Default")
      (node (ref "IC4") (pin "6") (pinfunction "CO_6") (pintype "output"))
    )
    (net (code "100") (name "unconnected-(IC4A-DO-Pad10)") (class "Default")
      (node (ref "IC4") (pin "10") (pinfunction "DO_10") (pintype "output"))
    )
    (net (code "101") (name "unconnected-(IC4A-EO-Pad12)") (class "Default")
      (node (ref "IC4") (pin "12") (pinfunction "EO_12") (pintype "output"))
    )
    (net (code "102") (name "unconnected-(IC4A-FO-Pad15)") (class "Default")
      (node (ref "IC4") (pin "15") (pinfunction "FO_15") (pintype "output"))
    )
    (net (code "103") (name "unconnected-(IC7B-Y4-Pad3)") (class "Default")
      (node (ref "IC7") (pin "3") (pinfunction "Y4_3") (pintype "tri_state"))
    )
    (net (code "104") (name "unconnected-(U2-CLKOUT-Pad3)") (class "Default")
      (node (ref "U2") (pin "3") (pinfunction "CLKOUT_3") (pintype "output"))
    )
    (net (code "105") (name "unconnected-(UEXT-Pad1)") (class "Default")
      (node (ref "UEXT") (pin "1") (pinfunction "1_1") (pintype "passive"))
    )
    (net (code "106") (name "~{PROBE_ISOLATED}") (class "Default")
      (node (ref "IC7") (pin "15") (pinfunction "A3_15") (pintype "input"))
      (node (ref "OK4") (pin "14") (pinfunction "COL_14") (pintype "passive"))
      (node (ref "R13") (pin "1") (pinfunction "1_1") (pintype "passive"))
    )
  )
)
